# top.net
KiCad netlist of a schematic drawn in Altium Designer
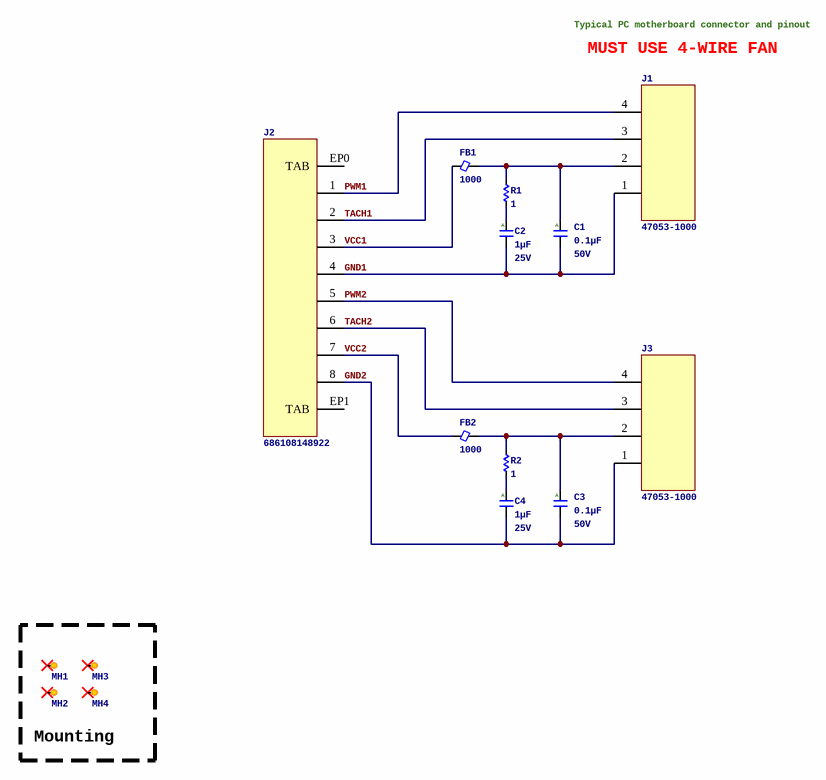
[diagram p0: top.SchDoc]

(export (version "E")
  (design (tool "Eeschema 10.0.6"))
  (components
    (comp (ref "C1")
      (value "CGA2B3X7R1H104M050BB")
      (footprint "C0402_0.55MM")
      (description "CAP CER 0.1UF 50V X7R 0402")
      (fields
        (field (name "CAPACITANCE") "0.1µF")
        (field (name "VOLTAGE - RATED") "50V")
        (field (name "TOLERANCE") "±20%")
        (field (name "MANUFACTURER") "TDK Corporation")
      )
      (libsource (lib "sscp") (part "__template_cap_auto"))
    )
    (comp (ref "C2")
      (value "CGJ3E1X7R1E105K080AC")
      (footprint "C0603_0.80MM")
      (description "CAP CER 1UF 25V X7R 0603")
      (fields
        (field (name "CAPACITANCE") "1µF")
        (field (name "VOLTAGE - RATED") "25V")
        (field (name "TOLERANCE") "±10%")
        (field (name "MANUFACTURER") "TDK Corporation")
      )
      (libsource (lib "sscp") (part "__template_cap_auto"))
    )
    (comp (ref "C3")
      (value "CGA2B3X7R1H104M050BB")
      (footprint "C0402_0.55MM")
      (description "CAP CER 0.1UF 50V X7R 0402")
      (fields
        (field (name "CAPACITANCE") "0.1µF")
        (field (name "VOLTAGE - RATED") "50V")
        (field (name "TOLERANCE") "±20%")
        (field (name "MANUFACTURER") "TDK Corporation")
      )
      (libsource (lib "sscp") (part "__template_cap_auto"))
    )
    (comp (ref "C4")
      (value "CGJ3E1X7R1E105K080AC")
      (footprint "C0603_0.80MM")
      (description "CAP CER 1UF 25V X7R 0603")
      (fields
        (field (name "CAPACITANCE") "1µF")
        (field (name "VOLTAGE - RATED") "25V")
        (field (name "TOLERANCE") "±10%")
        (field (name "MANUFACTURER") "TDK Corporation")
      )
      (libsource (lib "sscp") (part "__template_cap_auto"))
    )
    (comp (ref "FB1")
      (value "MPZ2012S102AT000")
      (footprint "FB0805_1.05MM")
      (description "FERRITE BEAD 1 KOHM 0805 1LN")
      (fields
        (field (name "IMPEDANCE (OHMS @ 100MHZ)") "1000")
        (field (name "MANUFACTURER") "TDK Corporation")
      )
      (libsource (lib "sscp") (part "__template_ferrite"))
    )
    (comp (ref "FB2")
      (value "MPZ2012S102AT000")
      (footprint "FB0805_1.05MM")
      (description "FERRITE BEAD 1 KOHM 0805 1LN")
      (fields
        (field (name "IMPEDANCE (OHMS @ 100MHZ)") "1000")
        (field (name "MANUFACTURER") "TDK Corporation")
      )
      (libsource (lib "sscp") (part "__template_ferrite"))
    )
    (comp (ref "J1")
      (value "47053-1000")
      (footprint "MOLEX_KK254_4POS_VERT_0470531000")
      (fields (field (name "MANUFACTURER") "Molex"))
      (libsource (lib "SSCP") (part "CONN_MOLEX_KK254_4POS_VERT_47053-1000"))
    )
    (comp (ref "J2")
      (value "686108148922")
      (footprint "WURTH_WR-FPC_1.00mm_686108148922")
      (description "WR-FPC 1mm SMT Horiz. Bot. Contact Hinge type")
      (fields (field (name "MANUFACTURER") "Wurth Elektronik"))
      (libsource (lib "SSCP") (part "CONN_WURTH_WR-FPC_8POS_1.00mm_686108148922"))
    )
    (comp (ref "J3")
      (value "47053-1000")
      (footprint "MOLEX_KK254_4POS_VERT_0470531000")
      (fields (field (name "MANUFACTURER") "Molex"))
      (libsource (lib "SSCP") (part "CONN_MOLEX_KK254_4POS_VERT_47053-1000"))
    )
    (comp (ref "MH1") (value "HOLE") (footprint "HOLE_M3") (libsource (lib "SSCP") (part "HOLE")))
    (comp (ref "MH2") (value "HOLE") (footprint "HOLE_M3") (libsource (lib "SSCP") (part "HOLE")))
    (comp (ref "MH3") (value "HOLE") (footprint "HOLE_M3") (libsource (lib "SSCP") (part "HOLE")))
    (comp (ref "MH4") (value "HOLE") (footprint "HOLE_M3") (libsource (lib "SSCP") (part "HOLE")))
    (comp (ref "R1")
      (value "ERJ-2BQF1R0X")
      (footprint "R0402_0.40MM")
      (description "RES SMD 1 OHM 1% 1/6W 0402")
      (fields
        (field (name "RESISTANCE") "1")
        (field (name "TOLERANCE") "±1%")
        (field (name "MANUFACTURER") "Panasonic Electronic Components")
      )
      (libsource (lib "sscp") (part "__template_resistor"))
    )
    (comp (ref "R2")
      (value "ERJ-2BQF1R0X")
      (footprint "R0402_0.40MM")
      (description "RES SMD 1 OHM 1% 1/6W 0402")
      (fields
        (field (name "RESISTANCE") "1")
        (field (name "TOLERANCE") "±1%")
        (field (name "MANUFACTURER") "Panasonic Electronic Components")
      )
      (libsource (lib "sscp") (part "__template_resistor"))
    )
  )
  (nets
    (net (code "1") (name "/GND1") (class "Default")
      (node (ref "C1") (pin "2") (pintype "passive"))
      (node (ref "C2") (pin "2") (pintype "passive"))
      (node (ref "J1") (pin "1") (pintype "passive"))
      (node (ref "J2") (pin "4") (pintype "passive"))
    )
    (net (code "2") (name "/GND2") (class "Default")
      (node (ref "C3") (pin "2") (pintype "passive"))
      (node (ref "C4") (pin "2") (pintype "passive"))
      (node (ref "J2") (pin "8") (pintype "passive"))
      (node (ref "J3") (pin "1") (pintype "passive"))
    )
    (net (code "3") (name "/PWM1") (class "Default")
      (node (ref "J1") (pin "4") (pintype "passive"))
      (node (ref "J2") (pin "1") (pintype "passive"))
    )
    (net (code "4") (name "/PWM2") (class "Default")
      (node (ref "J2") (pin "5") (pintype "passive"))
      (node (ref "J3") (pin "4") (pintype "passive"))
    )
    (net (code "5") (name "/TACH1") (class "Default")
      (node (ref "J1") (pin "3") (pintype "passive"))
      (node (ref "J2") (pin "2") (pintype "passive"))
    )
    (net (code "6") (name "/TACH2") (class "Default")
      (node (ref "J2") (pin "6") (pintype "passive"))
      (node (ref "J3") (pin "3") (pintype "passive"))
    )
    (net (code "7") (name "/VCC1") (class "Default")
      (node (ref "FB1") (pin "1") (pintype "passive"))
      (node (ref "J2") (pin "3") (pintype "passive"))
    )
    (net (code "8") (name "/VCC2") (class "Default")
      (node (ref "FB2") (pin "1") (pintype "passive"))
      (node (ref "J2") (pin "7") (pintype "passive"))
    )
    (net (code "9") (name "Net-(C1-Pad1)") (class "Default")
      (node (ref "C1") (pin "1") (pintype "passive"))
      (node (ref "FB1") (pin "2") (pintype "passive"))
      (node (ref "J1") (pin "2") (pintype "passive"))
      (node (ref "R1") (pin "2") (pintype "passive"))
    )
    (net (code "10") (name "Net-(C2-Pad1)") (class "Default")
      (node (ref "C2") (pin "1") (pintype "passive"))
      (node (ref "R1") (pin "1") (pintype "passive"))
    )
    (net (code "11") (name "Net-(C3-Pad1)") (class "Default")
      (node (ref "C3") (pin "1") (pintype "passive"))
      (node (ref "FB2") (pin "2") (pintype "passive"))
      (node (ref "J3") (pin "2") (pintype "passive"))
      (node (ref "R2") (pin "2") (pintype "passive"))
    )
    (net (code "12") (name "Net-(C4-Pad1)") (class "Default")
      (node (ref "C4") (pin "1") (pintype "passive"))
      (node (ref "R2") (pin "1") (pintype "passive"))
    )
    (net (code "13") (name "unconnected-(J2-TAB-PadEP0)") (class "Default")
      (node (ref "J2") (pin "EP0") (pinfunction "TAB_EP0") (pintype "passive"))
    )
    (net (code "14") (name "unconnected-(J2-TAB-PadEP1)") (class "Default")
      (node (ref "J2") (pin "EP1") (pinfunction "TAB_EP1") (pintype "passive"))
    )
    (net (code "15") (name "unconnected-(MH1-Pad1)") (class "Default")
      (node (ref "MH1") (pin "1") (pintype "passive+no_connect"))
    )
    (net (code "16") (name "unconnected-(MH2-Pad1)") (class "Default")
      (node (ref "MH2") (pin "1") (pintype "passive+no_connect"))
    )
    (net (code "17") (name "unconnected-(MH3-Pad1)") (class "Default")
      (node (ref "MH3") (pin "1") (pintype "passive+no_connect"))
    )
    (net (code "18") (name "unconnected-(MH4-Pad1)") (class "Default")
      (node (ref "MH4") (pin "1") (pintype "passive+no_connect"))
    )
  )
)
